# Support.net
KiCad netlist of a schematic drawn in Altium Designer
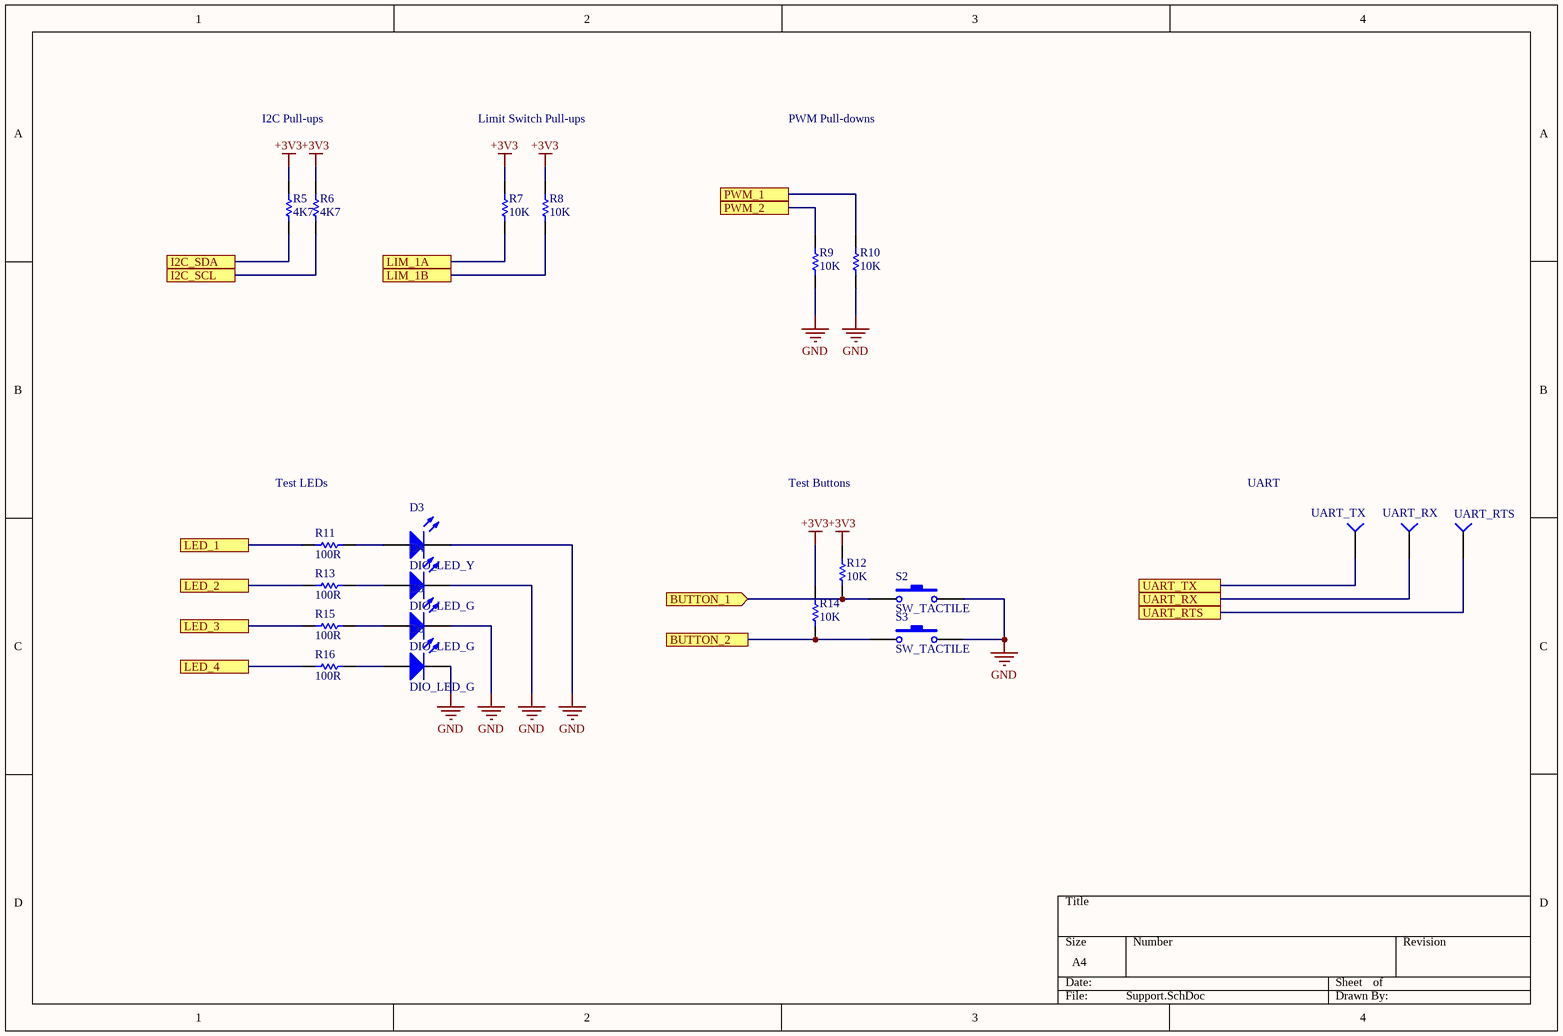
[diagram p0: Support.SchDoc]

(export (version "E")
  (design (tool "Eeschema 10.0.6"))
  (components
    (comp (ref "D3")
      (value "DIO_LED_Y")
      (footprint "LED_0805")
      (description "LED YELLOW DIFFUSED 0805 SMD")
      (fields (field (name "PART NUMBER") "LY R976-PS-36") (field (name "MANUFACTURER") "OSRAM"))
      (libsource (lib "UWRT_Schematic_Library_2019") (part "DIO_LED_Y"))
    )
    (comp (ref "D4")
      (value "DIO_LED_G")
      (footprint "LED_0805")
      (description "LED GREEN DIFFUSED 0805 SMD")
      (fields (field (name "PART NUMBER") "LG R971-KN-1") (field (name "MANUFACTURER") "OSRAM"))
      (libsource (lib "UWRT_Schematic_Library_2019") (part "DIO_LED_G"))
    )
    (comp (ref "D5")
      (value "DIO_LED_G")
      (footprint "LED_0805")
      (description "LED GREEN DIFFUSED 0805 SMD")
      (fields (field (name "PART NUMBER") "LG R971-KN-1") (field (name "MANUFACTURER") "OSRAM"))
      (libsource (lib "UWRT_Schematic_Library_2019") (part "DIO_LED_G"))
    )
    (comp (ref "D6")
      (value "DIO_LED_G")
      (footprint "LED_0805")
      (description "LED GREEN DIFFUSED 0805 SMD")
      (fields (field (name "PART NUMBER") "LG R971-KN-1") (field (name "MANUFACTURER") "OSRAM"))
      (libsource (lib "UWRT_Schematic_Library_2019") (part "DIO_LED_G"))
    )
    (comp (ref "R5")
      (value "4K7")
      (footprint "RESC0603(1608)_N")
      (description "RES SMD 4.7K OHM 5% 1/10W 0603")
      (fields (field (name "MANUFACTURER") "Yageo") (field (name "TOLERANCE") "5%"))
      (libsource (lib "UWRT_Schematic_Library_2019") (part "RES_4K7_0603"))
    )
    (comp (ref "R6")
      (value "4K7")
      (footprint "RESC0603(1608)_N")
      (description "RES SMD 4.7K OHM 5% 1/10W 0603")
      (fields (field (name "MANUFACTURER") "Yageo") (field (name "TOLERANCE") "5%"))
      (libsource (lib "UWRT_Schematic_Library_2019") (part "RES_4K7_0603"))
    )
    (comp (ref "R7")
      (value "10K")
      (footprint "RESC0603(1608)_N")
      (description "RES SMD 10K OHM 5% 1/10W 0603")
      (fields (field (name "MANUFACTURER") "Yageo") (field (name "TOLERANCE") "5%"))
      (libsource (lib "UWRT_Schematic_Library_2019") (part "RES_10K_0603"))
    )
    (comp (ref "R8")
      (value "10K")
      (footprint "RESC0603(1608)_N")
      (description "RES SMD 10K OHM 5% 1/10W 0603")
      (fields (field (name "MANUFACTURER") "Yageo") (field (name "TOLERANCE") "5%"))
      (libsource (lib "UWRT_Schematic_Library_2019") (part "RES_10K_0603"))
    )
    (comp (ref "R9")
      (value "10K")
      (footprint "RESC0603(1608)_N")
      (description "RES SMD 10K OHM 5% 1/10W 0603")
      (fields (field (name "MANUFACTURER") "Yageo") (field (name "TOLERANCE") "5%"))
      (libsource (lib "UWRT_Schematic_Library_2019") (part "RES_10K_0603"))
    )
    (comp (ref "R10")
      (value "10K")
      (footprint "RESC0603(1608)_N")
      (description "RES SMD 10K OHM 5% 1/10W 0603")
      (fields (field (name "MANUFACTURER") "Yageo") (field (name "TOLERANCE") "5%"))
      (libsource (lib "UWRT_Schematic_Library_2019") (part "RES_10K_0603"))
    )
    (comp (ref "R11")
      (value "100R")
      (footprint "RESC0603(1608)_N")
      (description "RES SMD 100 OHM 1% 1/10W 0603")
      (fields (field (name "MANUFACTURER") "Yageo") (field (name "TOLERANCE") "1%"))
      (libsource (lib "UWRT_Schematic_Library_2019") (part "RES_100R_0603"))
    )
    (comp (ref "R12")
      (value "10K")
      (footprint "RESC0603(1608)_N")
      (description "RES SMD 10K OHM 5% 1/10W 0603")
      (fields (field (name "MANUFACTURER") "Yageo") (field (name "TOLERANCE") "5%"))
      (libsource (lib "UWRT_Schematic_Library_2019") (part "RES_10K_0603"))
    )
    (comp (ref "R13")
      (value "100R")
      (footprint "RESC0603(1608)_N")
      (description "RES SMD 100 OHM 1% 1/10W 0603")
      (fields (field (name "MANUFACTURER") "Yageo") (field (name "TOLERANCE") "1%"))
      (libsource (lib "UWRT_Schematic_Library_2019") (part "RES_100R_0603"))
    )
    (comp (ref "R14")
      (value "10K")
      (footprint "RESC0603(1608)_N")
      (description "RES SMD 10K OHM 5% 1/10W 0603")
      (fields (field (name "MANUFACTURER") "Yageo") (field (name "TOLERANCE") "5%"))
      (libsource (lib "UWRT_Schematic_Library_2019") (part "RES_10K_0603"))
    )
    (comp (ref "R15")
      (value "100R")
      (footprint "RESC0603(1608)_N")
      (description "RES SMD 100 OHM 1% 1/10W 0603")
      (fields (field (name "MANUFACTURER") "Yageo") (field (name "TOLERANCE") "1%"))
      (libsource (lib "UWRT_Schematic_Library_2019") (part "RES_100R_0603"))
    )
    (comp (ref "R16")
      (value "100R")
      (footprint "RESC0603(1608)_N")
      (description "RES SMD 100 OHM 1% 1/10W 0603")
      (fields (field (name "MANUFACTURER") "Yageo") (field (name "TOLERANCE") "1%"))
      (libsource (lib "UWRT_Schematic_Library_2019") (part "RES_100R_0603"))
    )
    (comp (ref "S2")
      (value "SW_TACTILE")
      (footprint "B3U-1100P")
      (description "Tactile Switch (Grey)")
      (fields
        (field (name "MANUFACTURER PART NUMBER") "B3U-1100P")
        (field (name "DIGIKEY PART NUMBER") "SW1021TR-ND")
      )
      (libsource (lib "UWRT_Schematic_Library_2019") (part "SW_TACTILE"))
    )
    (comp (ref "S3")
      (value "SW_TACTILE")
      (footprint "B3U-1100P")
      (description "Tactile Switch (Grey)")
      (fields
        (field (name "MANUFACTURER PART NUMBER") "B3U-1100P")
        (field (name "DIGIKEY PART NUMBER") "SW1021TR-ND")
      )
      (libsource (lib "UWRT_Schematic_Library_2019") (part "SW_TACTILE"))
    )
    (comp (ref "UART_RTS")
      (value "TESTPOINT")
      (libsource (lib "UWRT_Schematic_Library_2019") (part "TESTPOINT"))
    )
    (comp (ref "UART_RX")
      (value "TESTPOINT")
      (libsource (lib "UWRT_Schematic_Library_2019") (part "TESTPOINT"))
    )
    (comp (ref "UART_TX")
      (value "TESTPOINT")
      (libsource (lib "UWRT_Schematic_Library_2019") (part "TESTPOINT"))
    )
  )
  (nets
    (net (code "1") (name "+3V3") (class "Default")
      (node (ref "R12") (pin "2") (pinfunction "2_2") (pintype "passive"))
      (node (ref "R14") (pin "1") (pinfunction "1_1") (pintype "passive"))
      (node (ref "R5") (pin "2") (pinfunction "2_2") (pintype "passive"))
      (node (ref "R6") (pin "2") (pinfunction "2_2") (pintype "passive"))
      (node (ref "R7") (pin "2") (pinfunction "2_2") (pintype "passive"))
      (node (ref "R8") (pin "2") (pinfunction "2_2") (pintype "passive"))
    )
    (net (code "2") (name "/BUTTON_1") (class "Default")
      (node (ref "R12") (pin "1") (pinfunction "1_1") (pintype "passive"))
      (node (ref "S2") (pin "1") (pinfunction "1_1") (pintype "passive"))
    )
    (net (code "3") (name "/BUTTON_2") (class "Default")
      (node (ref "R14") (pin "2") (pinfunction "2_2") (pintype "passive"))
      (node (ref "S3") (pin "1") (pinfunction "1_1") (pintype "passive"))
    )
    (net (code "4") (name "/I2C_SCL") (class "Default")
      (node (ref "R6") (pin "1") (pinfunction "1_1") (pintype "passive"))
    )
    (net (code "5") (name "/I2C_SDA") (class "Default")
      (node (ref "R5") (pin "1") (pinfunction "1_1") (pintype "passive"))
    )
    (net (code "6") (name "/LED_1") (class "Default")
      (node (ref "R11") (pin "1") (pinfunction "1_1") (pintype "passive"))
    )
    (net (code "7") (name "/LED_2") (class "Default")
      (node (ref "R13") (pin "1") (pinfunction "1_1") (pintype "passive"))
    )
    (net (code "8") (name "/LED_3") (class "Default")
      (node (ref "R15") (pin "1") (pinfunction "1_1") (pintype "passive"))
    )
    (net (code "9") (name "/LED_4") (class "Default")
      (node (ref "R16") (pin "1") (pinfunction "1_1") (pintype "passive"))
    )
    (net (code "10") (name "/LIM_1A") (class "Default")
      (node (ref "R7") (pin "1") (pinfunction "1_1") (pintype "passive"))
    )
    (net (code "11") (name "/LIM_1B") (class "Default")
      (node (ref "R8") (pin "1") (pinfunction "1_1") (pintype "passive"))
    )
    (net (code "12") (name "/PWM_1") (class "Default")
      (node (ref "R10") (pin "2") (pinfunction "2_2") (pintype "passive"))
    )
    (net (code "13") (name "/PWM_2") (class "Default")
      (node (ref "R9") (pin "2") (pinfunction "2_2") (pintype "passive"))
    )
    (net (code "14") (name "/UART_RTS") (class "Default")
      (node (ref "UART_RTS") (pin "1") (pinfunction "=value_1") (pintype "passive"))
    )
    (net (code "15") (name "/UART_RX") (class "Default")
      (node (ref "UART_RX") (pin "1") (pinfunction "=value_1") (pintype "passive"))
    )
    (net (code "16") (name "/UART_TX") (class "Default")
      (node (ref "UART_TX") (pin "1") (pinfunction "=value_1") (pintype "passive"))
    )
    (net (code "17") (name "GND") (class "Default")
      (node (ref "D3") (pin "2") (pinfunction "K_2") (pintype "passive"))
      (node (ref "D4") (pin "2") (pinfunction "K_2") (pintype "passive"))
      (node (ref "D5") (pin "2") (pinfunction "K_2") (pintype "passive"))
      (node (ref "D6") (pin "2") (pinfunction "K_2") (pintype "passive"))
      (node (ref "R10") (pin "1") (pinfunction "1_1") (pintype "passive"))
      (node (ref "R9") (pin "1") (pinfunction "1_1") (pintype "passive"))
      (node (ref "S2") (pin "2") (pinfunction "2_2") (pintype "passive"))
      (node (ref "S3") (pin "2") (pinfunction "2_2") (pintype "passive"))
    )
    (net (code "18") (name "Net-(D3-A)") (class "Default")
      (node (ref "D3") (pin "1") (pinfunction "A_1") (pintype "passive"))
      (node (ref "R11") (pin "2") (pinfunction "2_2") (pintype "passive"))
    )
    (net (code "19") (name "Net-(D4-A)") (class "Default")
      (node (ref "D4") (pin "1") (pinfunction "A_1") (pintype "passive"))
      (node (ref "R13") (pin "2") (pinfunction "2_2") (pintype "passive"))
    )
    (net (code "20") (name "Net-(D5-A)") (class "Default")
      (node (ref "D5") (pin "1") (pinfunction "A_1") (pintype "passive"))
      (node (ref "R15") (pin "2") (pinfunction "2_2") (pintype "passive"))
    )
    (net (code "21") (name "Net-(D6-A)") (class "Default")
      (node (ref "D6") (pin "1") (pinfunction "A_1") (pintype "passive"))
      (node (ref "R16") (pin "2") (pinfunction "2_2") (pintype "passive"))
    )
  )
)
